# 01_Power_Control.net
KiCad netlist of a schematic drawn in Altium Designer
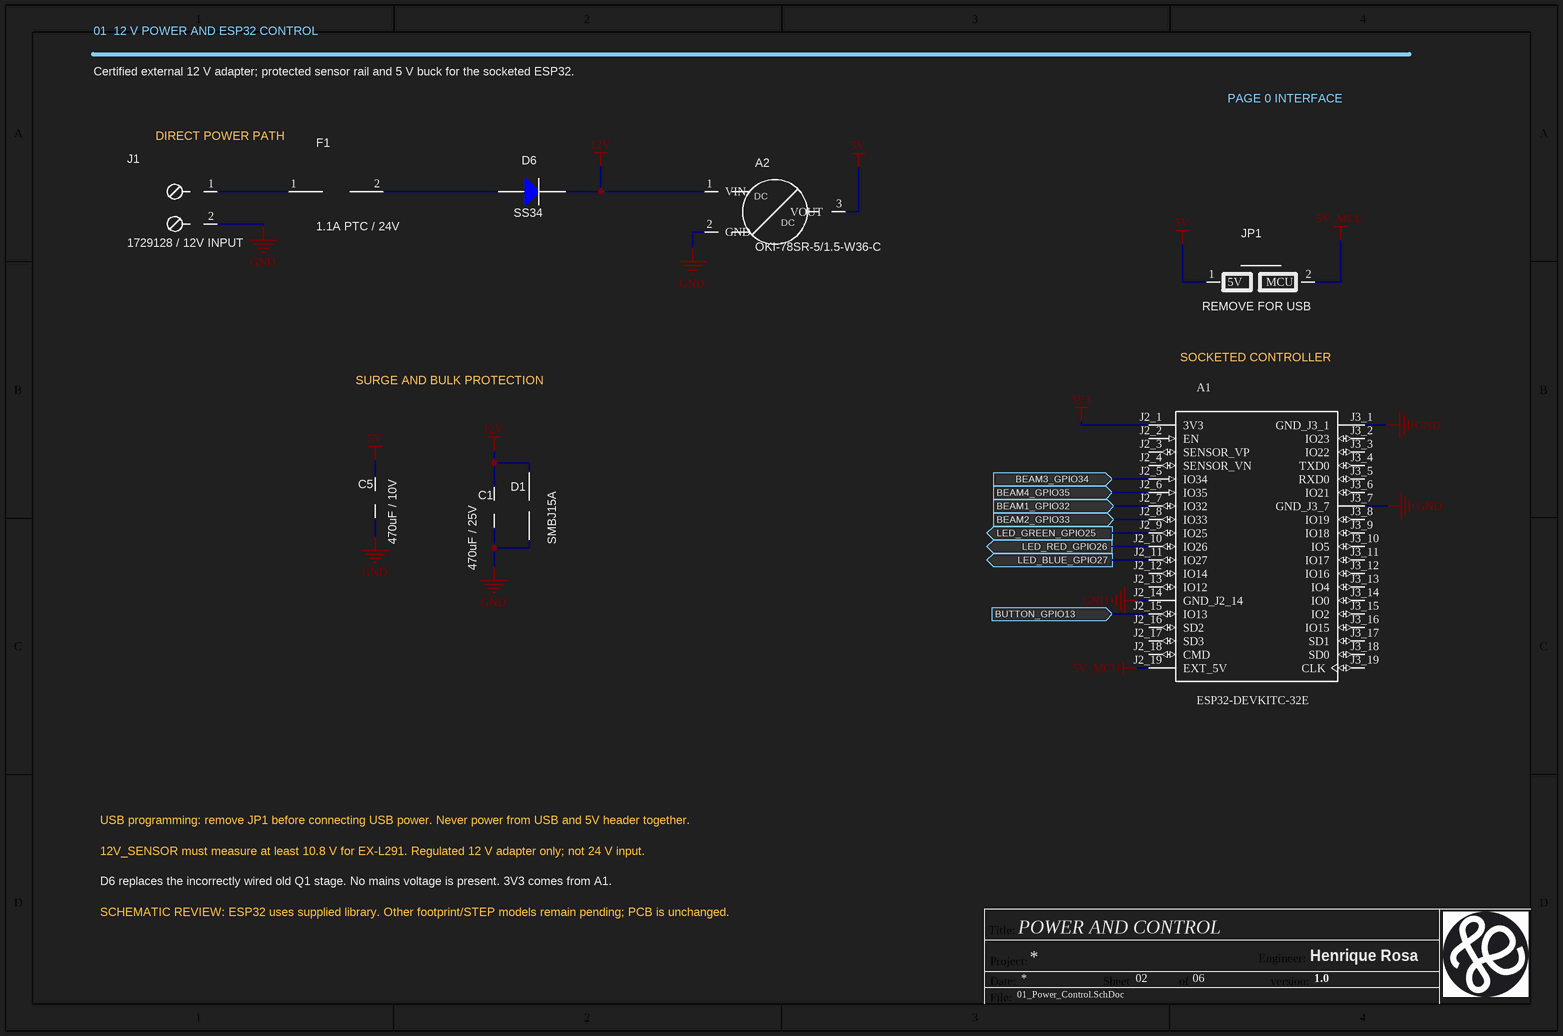
[diagram p0: 01_Power_Control.SchDoc]

(export (version "E")
  (design (tool "Eeschema 10.0.6"))
  (components
    (comp (ref "A1")
      (value "ESP32-DEVKITC-32E")
      (footprint "MODULE_ESP32-DEVKITC-32E:MODULE_ESP32-DEVKITC-32E")
      (fields
        (field (name "MF") "Espressif Systems")
        (field (name "MANUFACTURER PART NUMBER") "ESP32-DevKitC-32E")
      )
      (libsource (lib "ReviewedComponents_20260912-233454") (part "ESP32-DevKitC-32E__A1_view"))
    )
    (comp (ref "A2")
      (value "OKI-78SR-5/1.5-W36-C")
      (footprint "PartSpecificFootprints:MURATA_OKI78SR_VERTICAL")
      (description "12 V to regulated 5 V DC/DC module")
      (fields (field (name "MANUFACTURER") "Murata"))
      (libsource (lib "ReviewedComponents_20260912-233454") (part "OKI-78SR-5_1_5-W36-C__A2_view"))
    )
    (comp (ref "C1")
      (value "470uF / 25V")
      (footprint "PinRepairFootprints:PANASONIC_EEUFR1E471_D10_P5")
      (description "Protected 12 V bulk capacitor")
      (fields (field (name "PART NUMBER") "EEU-FR1E471") (field (name "MANUFACTURER") "Panasonic"))
      (libsource (lib "ReviewedComponents_20260912-233454") (part "EEU-FR1E471__C1_view"))
    )
    (comp (ref "C5")
      (value "470uF / 10V")
      (footprint "PinRepairFootprints:PANASONIC_EEUFR1A471_D8_P3_5")
      (description "ESP32 Wi-Fi peak-current reservoir")
      (fields (field (name "PART NUMBER") "EEU-FR1A471") (field (name "MANUFACTURER") "Panasonic"))
      (libsource (lib "ReviewedComponents_20260912-233454") (part "EEU-FR1A471__C5_view"))
    )
    (comp (ref "D1")
      (value "SMBJ15A")
      (footprint "PinRepairFootprints:SMBJ15A_A1_K2")
      (description "15 V TVS suppressor - cathode to positive rail")
      (fields (field (name "MANUFACTURER") "Littelfuse"))
      (libsource (lib "ReviewedComponents_20260912-233454") (part "SMBJ15A__D1_view"))
    )
    (comp (ref "D6")
      (value "SS34")
      (footprint "PinRepairFootprints:SS34_A1_K2")
      (description "Series reverse-polarity Schottky diode")
      (fields (field (name "PART NUMBER") "SS34-E3/57T") (field (name "MANUFACTURER") "Vishay"))
      (libsource (lib "ReviewedComponents_20260912-233454") (part "SS34-E3_57T__D6_view"))
    )
    (comp (ref "F1")
      (value "1.1A PTC / 24V")
      (footprint "PinRepairFootprints:BOURNS_MFMSMF110_24X_STYLE2")
      (description "Resettable 12 V input fuse")
      (fields
        (field (name "MANUFACTURER") "Bourns")
        (field (name "MANUFACTURER PART NUMBER") "MF-MSMF110/24X-2")
      )
      (libsource (lib "ReviewedComponents_20260912-233454") (part "MF-MSMF110_24X-2__F1_view"))
    )
    (comp (ref "J1")
      (value "1729128 / 12V INPUT")
      (footprint "PartSpecificFootprints:PHOENIX_1729128_MKDSN_2_508")
      (description "Two-position 5.08 mm screw terminal")
      (fields
        (field (name "MANUFACTURER") "Phoenix Contact")
        (field (name "MANUFACTURER PART NUMBER") "1729128")
      )
      (libsource (lib "ReviewedComponents_20260912-233454") (part "1729128__J1_view"))
    )
    (comp (ref "JP1")
      (value "REMOVE FOR USB")
      (footprint "PinRepairFootprints:SAMTEC_TSW102_07_SINGLE")
      (description "External 5 V disconnect; fit shunt only without USB")
      (fields
        (field (name "MANUFACTURER") "Samtec")
        (field (name "MANUFACTURER PART NUMBER") "TSW-102-07-G-S")
      )
      (libsource (lib "ReviewedComponents_20260912-233454") (part "TSW-102-07-G-S__JP1_view"))
    )
  )
  (nets
    (net (code "1") (name "/BEAM1_GPIO32") (class "Default")
      (node (ref "A1") (pin "J2_7") (pinfunction "IO32_J2_7") (pintype "bidirectional"))
    )
    (net (code "2") (name "/BEAM2_GPIO33") (class "Default")
      (node (ref "A1") (pin "J2_8") (pinfunction "IO33_J2_8") (pintype "bidirectional"))
    )
    (net (code "3") (name "/BEAM3_GPIO34") (class "Default")
      (node (ref "A1") (pin "J2_5") (pinfunction "IO34_J2_5") (pintype "input"))
    )
    (net (code "4") (name "/BEAM4_GPIO35") (class "Default")
      (node (ref "A1") (pin "J2_6") (pinfunction "IO35_J2_6") (pintype "input"))
    )
    (net (code "5") (name "/BUTTON_GPIO13") (class "Default")
      (node (ref "A1") (pin "J2_15") (pinfunction "IO13_J2_15") (pintype "bidirectional"))
    )
    (net (code "6") (name "/LED_BLUE_GPIO27") (class "Default")
      (node (ref "A1") (pin "J2_11") (pinfunction "IO27_J2_11") (pintype "bidirectional"))
    )
    (net (code "7") (name "/LED_GREEN_GPIO25") (class "Default")
      (node (ref "A1") (pin "J2_9") (pinfunction "IO25_J2_9") (pintype "bidirectional"))
    )
    (net (code "8") (name "/LED_RED_GPIO26") (class "Default")
      (node (ref "A1") (pin "J2_10") (pinfunction "IO26_J2_10") (pintype "bidirectional"))
    )
    (net (code "9") (name "3V3") (class "Default")
      (node (ref "A1") (pin "J2_1") (pinfunction "3V3_J2_1") (pintype "power_in"))
    )
    (net (code "10") (name "5V") (class "Default")
      (node (ref "A2") (pin "3") (pinfunction "VOUT_3") (pintype "passive"))
      (node (ref "C5") (pin "2") (pinfunction "2_2") (pintype "passive"))
      (node (ref "JP1") (pin "1") (pinfunction "5V_1") (pintype "passive"))
    )
    (net (code "11") (name "5V_MCU") (class "Default")
      (node (ref "A1") (pin "J2_19") (pinfunction "EXT_5V_J2_19") (pintype "power_in"))
      (node (ref "JP1") (pin "2") (pinfunction "MCU_2") (pintype "passive"))
    )
    (net (code "12") (name "12V") (class "Default")
      (node (ref "A2") (pin "1") (pinfunction "VIN_1") (pintype "passive"))
      (node (ref "C1") (pin "2") (pinfunction "2_2") (pintype "passive"))
      (node (ref "D1") (pin "2") (pinfunction "K_2") (pintype "passive"))
      (node (ref "D6") (pin "2") (pinfunction "K_2") (pintype "passive"))
    )
    (net (code "13") (name "GND") (class "Default")
      (node (ref "A1") (pin "J2_14") (pinfunction "GND_J2_14_J2_14") (pintype "power_in"))
      (node (ref "A1") (pin "J3_1") (pinfunction "GND_J3_1_J3_1") (pintype "power_in"))
      (node (ref "A1") (pin "J3_7") (pinfunction "GND_J3_7_J3_7") (pintype "power_in"))
      (node (ref "A2") (pin "2") (pinfunction "GND_2") (pintype "passive"))
      (node (ref "C1") (pin "1") (pinfunction "1_1") (pintype "passive"))
      (node (ref "C5") (pin "1") (pinfunction "1_1") (pintype "passive"))
      (node (ref "D1") (pin "1") (pinfunction "A_1") (pintype "passive"))
      (node (ref "J1") (pin "2") (pinfunction "0V_2") (pintype "power_in"))
    )
    (net (code "14") (name "Net-(D6-A)") (class "Default")
      (node (ref "D6") (pin "1") (pinfunction "A_1") (pintype "passive"))
      (node (ref "F1") (pin "2") (pintype "passive"))
    )
    (net (code "15") (name "Net-(J1-+12V)") (class "Default")
      (node (ref "F1") (pin "1") (pintype "passive"))
      (node (ref "J1") (pin "1") (pinfunction "+12V_1") (pintype "power_in"))
    )
    (net (code "16") (name "unconnected-(A1-CLK-PadJ3_19)") (class "Default")
      (node (ref "A1") (pin "J3_19") (pinfunction "CLK_J3_19") (pintype "bidirectional"))
    )
    (net (code "17") (name "unconnected-(A1-CMD-PadJ2_18)") (class "Default")
      (node (ref "A1") (pin "J2_18") (pinfunction "CMD_J2_18") (pintype "bidirectional"))
    )
    (net (code "18") (name "unconnected-(A1-EN-PadJ2_2)") (class "Default")
      (node (ref "A1") (pin "J2_2") (pinfunction "EN_J2_2") (pintype "input"))
    )
    (net (code "19") (name "unconnected-(A1-IO0-PadJ3_14)") (class "Default")
      (node (ref "A1") (pin "J3_14") (pinfunction "IO0_J3_14") (pintype "bidirectional"))
    )
    (net (code "20") (name "unconnected-(A1-IO2-PadJ3_15)") (class "Default")
      (node (ref "A1") (pin "J3_15") (pinfunction "IO2_J3_15") (pintype "bidirectional"))
    )
    (net (code "21") (name "unconnected-(A1-IO4-PadJ3_13)") (class "Default")
      (node (ref "A1") (pin "J3_13") (pinfunction "IO4_J3_13") (pintype "bidirectional"))
    )
    (net (code "22") (name "unconnected-(A1-IO5-PadJ3_10)") (class "Default")
      (node (ref "A1") (pin "J3_10") (pinfunction "IO5_J3_10") (pintype "bidirectional"))
    )
    (net (code "23") (name "unconnected-(A1-IO12-PadJ2_13)") (class "Default")
      (node (ref "A1") (pin "J2_13") (pinfunction "IO12_J2_13") (pintype "bidirectional"))
    )
    (net (code "24") (name "unconnected-(A1-IO14-PadJ2_12)") (class "Default")
      (node (ref "A1") (pin "J2_12") (pinfunction "IO14_J2_12") (pintype "bidirectional"))
    )
    (net (code "25") (name "unconnected-(A1-IO15-PadJ3_16)") (class "Default")
      (node (ref "A1") (pin "J3_16") (pinfunction "IO15_J3_16") (pintype "bidirectional"))
    )
    (net (code "26") (name "unconnected-(A1-IO16-PadJ3_12)") (class "Default")
      (node (ref "A1") (pin "J3_12") (pinfunction "IO16_J3_12") (pintype "bidirectional"))
    )
    (net (code "27") (name "unconnected-(A1-IO17-PadJ3_11)") (class "Default")
      (node (ref "A1") (pin "J3_11") (pinfunction "IO17_J3_11") (pintype "bidirectional"))
    )
    (net (code "28") (name "unconnected-(A1-IO18-PadJ3_9)") (class "Default")
      (node (ref "A1") (pin "J3_9") (pinfunction "IO18_J3_9") (pintype "bidirectional"))
    )
    (net (code "29") (name "unconnected-(A1-IO19-PadJ3_8)") (class "Default")
      (node (ref "A1") (pin "J3_8") (pinfunction "IO19_J3_8") (pintype "bidirectional"))
    )
    (net (code "30") (name "unconnected-(A1-IO21-PadJ3_6)") (class "Default")
      (node (ref "A1") (pin "J3_6") (pinfunction "IO21_J3_6") (pintype "bidirectional"))
    )
    (net (code "31") (name "unconnected-(A1-IO22-PadJ3_3)") (class "Default")
      (node (ref "A1") (pin "J3_3") (pinfunction "IO22_J3_3") (pintype "bidirectional"))
    )
    (net (code "32") (name "unconnected-(A1-IO23-PadJ3_2)") (class "Default")
      (node (ref "A1") (pin "J3_2") (pinfunction "IO23_J3_2") (pintype "bidirectional"))
    )
    (net (code "33") (name "unconnected-(A1-RXD0-PadJ3_5)") (class "Default")
      (node (ref "A1") (pin "J3_5") (pinfunction "RXD0_J3_5") (pintype "bidirectional"))
    )
    (net (code "34") (name "unconnected-(A1-SD0-PadJ3_18)") (class "Default")
      (node (ref "A1") (pin "J3_18") (pinfunction "SD0_J3_18") (pintype "bidirectional"))
    )
    (net (code "35") (name "unconnected-(A1-SD1-PadJ3_17)") (class "Default")
      (node (ref "A1") (pin "J3_17") (pinfunction "SD1_J3_17") (pintype "bidirectional"))
    )
    (net (code "36") (name "unconnected-(A1-SD2-PadJ2_16)") (class "Default")
      (node (ref "A1") (pin "J2_16") (pinfunction "SD2_J2_16") (pintype "bidirectional"))
    )
    (net (code "37") (name "unconnected-(A1-SD3-PadJ2_17)") (class "Default")
      (node (ref "A1") (pin "J2_17") (pinfunction "SD3_J2_17") (pintype "bidirectional"))
    )
    (net (code "38") (name "unconnected-(A1-SENSOR_VN-PadJ2_4)") (class "Default")
      (node (ref "A1") (pin "J2_4") (pinfunction "SENSOR_VN_J2_4") (pintype "bidirectional"))
    )
    (net (code "39") (name "unconnected-(A1-SENSOR_VP-PadJ2_3)") (class "Default")
      (node (ref "A1") (pin "J2_3") (pinfunction "SENSOR_VP_J2_3") (pintype "bidirectional"))
    )
    (net (code "40") (name "unconnected-(A1-TXD0-PadJ3_4)") (class "Default")
      (node (ref "A1") (pin "J3_4") (pinfunction "TXD0_J3_4") (pintype "bidirectional"))
    )
  )
)
